# Spin_SCH.net
KiCad netlist of a schematic drawn in Altium Designer
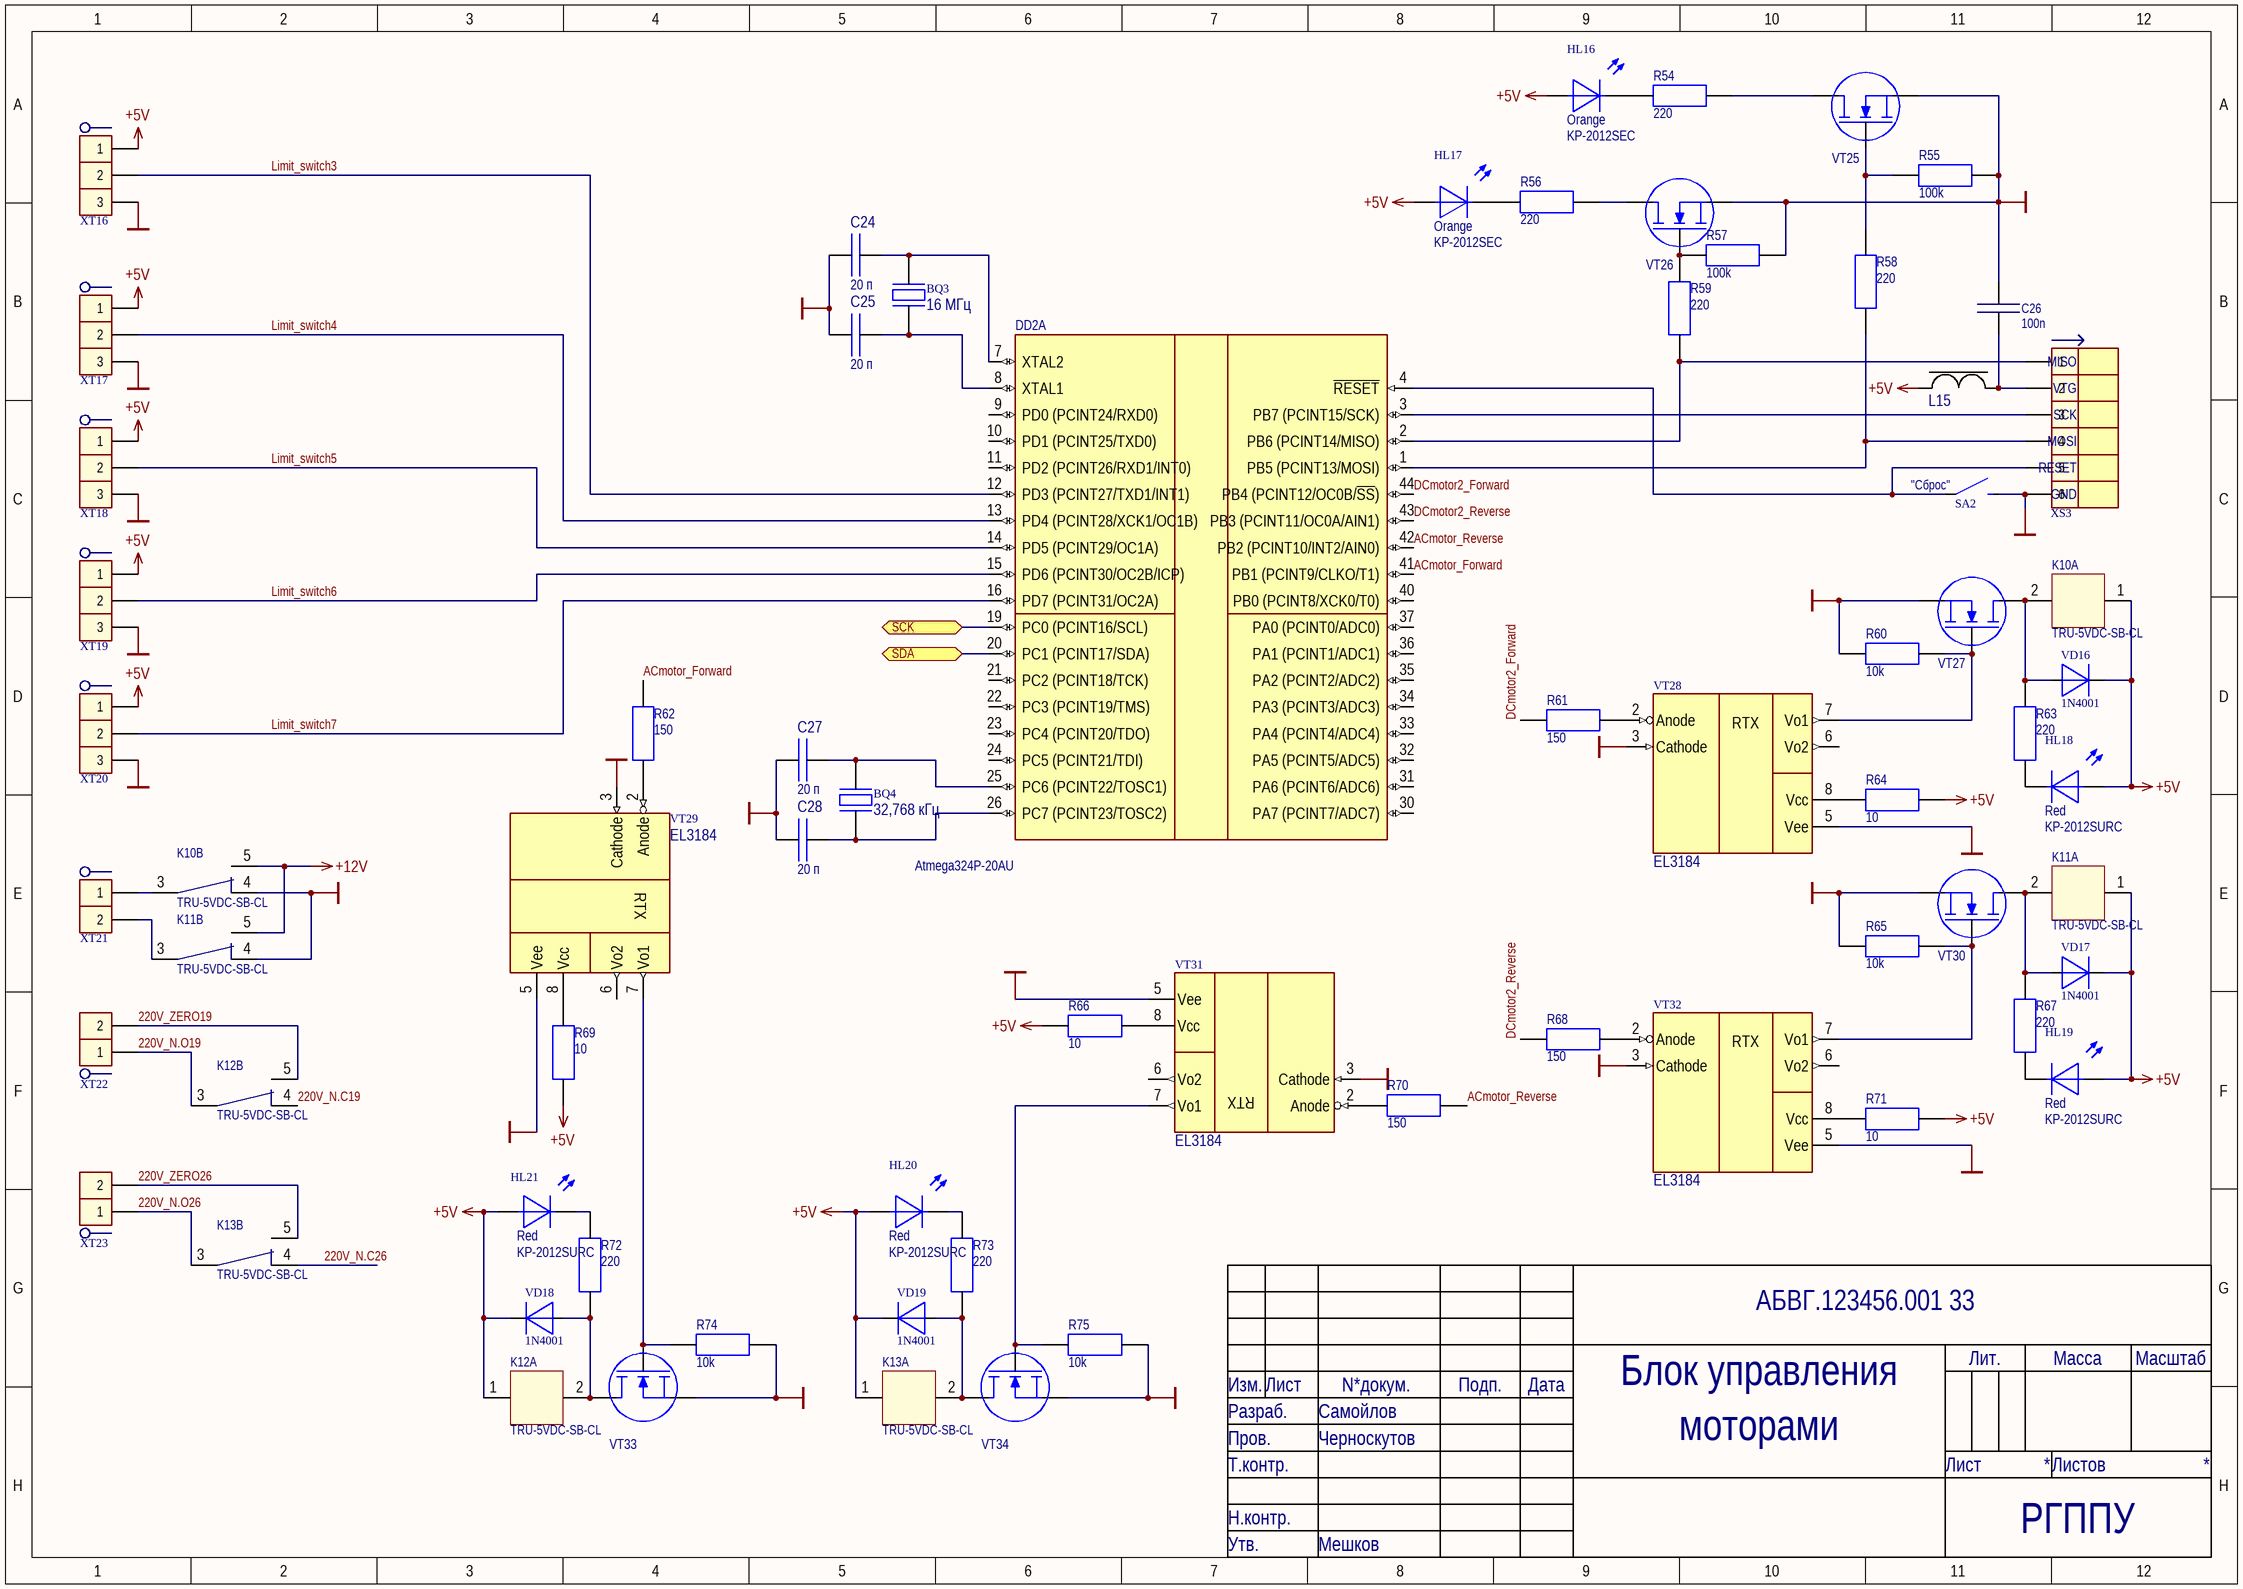
[diagram p0: Spin_SCH.SchDoc]

(export (version "E")
  (design (tool "Eeschema 10.0.6"))
  (components
    (comp (ref "BQ3")
      (value "16 МГц")
      (footprint "Piezoelectric:HC-49/S")
      (description "Piezoelectric elements")
      (fields
        (field (name "MANUFACTURER") "Taizhou")
        (field (name "MANUFACTURERPARTNUMBER") "16000 кГц 20ppm 20pF")
      )
      (libsource (lib "Piezoelectric") (part "Piezoelectric_16000"))
    )
    (comp (ref "BQ4")
      (value "32,768 кГц")
      (footprint "Piezoelectric:HC-49/S")
      (description "Piezoelectric elements")
      (fields
        (field (name "MANUFACTURER") "Taizhou")
        (field (name "MANUFACTURERPARTNUMBER") "16000 кГц 20ppm 20pF")
      )
      (libsource (lib "Piezoelectric") (part "Piezoelectric_16000"))
    )
    (comp (ref "C24")
      (value "20 п")
      (footprint "Cap:CAPC3216X05M")
      (description "20pF Bipolar cap")
      (fields
        (field (name "MANUFACTURERPARTNUMBER") "CC0603JRNP09BN200")
        (field (name "MANUFACTURER") "Yageo")
      )
      (libsource (lib "Cap") (part "p00020_050"))
    )
    (comp (ref "C25")
      (value "20 п")
      (footprint "Cap:CAPC3216X05M")
      (description "20pF Bipolar cap")
      (fields
        (field (name "MANUFACTURERPARTNUMBER") "CC0603JRNP09BN200")
        (field (name "MANUFACTURER") "Yageo")
      )
      (libsource (lib "Cap") (part "p00020_050"))
    )
    (comp (ref "C26")
      (value "100n")
      (footprint "SMDRC0805")
      (description "Generic capasitor non-polar")
      (fields (field (name "PARTNUMBER") "Capacitor 0805 100n"))
      (libsource (lib "library") (part "Capacitor"))
    )
    (comp (ref "C27")
      (value "20 п")
      (footprint "Cap:CAPC3216X05M")
      (description "20pF Bipolar cap")
      (fields
        (field (name "MANUFACTURERPARTNUMBER") "CC0603JRNP09BN200")
        (field (name "MANUFACTURER") "Yageo")
      )
      (libsource (lib "Cap") (part "p00020_050"))
    )
    (comp (ref "C28")
      (value "20 п")
      (footprint "Cap:CAPC3216X05M")
      (description "20pF Bipolar cap")
      (fields
        (field (name "MANUFACTURERPARTNUMBER") "CC0603JRNP09BN200")
        (field (name "MANUFACTURER") "Yageo")
      )
      (libsource (lib "Cap") (part "p00020_050"))
    )
    (comp (ref "DD2")
      (value "Atmega324P-20AU")
      (footprint "Atmel Microcontroller 8-Bit Automotive AVR:44ML_M")
      (description "Microcontroller 8-bit")
      (fields (field (name "MANUFACTURER") "Atmel") (field (name "MANUFACTURERPARTNUMBER") "Atmega324P-20AU"))
      (libsource (lib "Microcontrollers") (part "Atmega324P-20AU"))
    )
    (comp (ref "HL16")
      (value "Orange")
      (footprint "Indicator:DIOMELF2012M")
      (description "Diod LED SMD Orange")
      (fields (field (name "MANUFACTURERPARTNUMBER") "KP-2012SEC"))
      (libsource (lib "Indicator") (part "LED1_O"))
    )
    (comp (ref "HL17")
      (value "Orange")
      (footprint "Indicator:DIOMELF2012M")
      (description "Diod LED SMD Orange")
      (fields (field (name "MANUFACTURERPARTNUMBER") "KP-2012SEC"))
      (libsource (lib "Indicator") (part "LED1_O"))
    )
    (comp (ref "HL18")
      (value "Red")
      (footprint "Indicator:DIOMELF2012M")
      (description "Diod LED SMD Red")
      (fields (field (name "MANUFACTURERPARTNUMBER") "KP-2012SURC"))
      (libsource (lib "") (part "LED1_R_1"))
    )
    (comp (ref "HL19")
      (value "Red")
      (footprint "Indicator:DIOMELF2012M")
      (description "Diod LED SMD Red")
      (fields (field (name "MANUFACTURERPARTNUMBER") "KP-2012SURC"))
      (libsource (lib "") (part "LED1_R_1"))
    )
    (comp (ref "HL20")
      (value "Red")
      (footprint "Indicator:DIOMELF2012M")
      (description "Diod LED SMD Red")
      (fields (field (name "MANUFACTURERPARTNUMBER") "KP-2012SURC"))
      (libsource (lib "Indicator") (part "LED1_R"))
    )
    (comp (ref "HL21")
      (value "Red")
      (footprint "Indicator:DIOMELF2012M")
      (description "Diod LED SMD Red")
      (fields (field (name "MANUFACTURERPARTNUMBER") "KP-2012SURC"))
      (libsource (lib "Indicator") (part "LED1_R"))
    )
    (comp (ref "K10")
      (value "TRU-5VDC-SB-CL")
      (footprint "Switch:TRU-5VDC-SB-CL")
      (libsource (lib "") (part "TRU-5VDC-SB-CL_2"))
    )
    (comp (ref "K11")
      (value "TRU-5VDC-SB-CL")
      (footprint "Switch:TRU-5VDC-SB-CL")
      (libsource (lib "") (part "TRU-5VDC-SB-CL_2"))
    )
    (comp (ref "K12")
      (value "TRU-5VDC-SB-CL")
      (footprint "Switch:TRU-5VDC-SB-CL")
      (libsource (lib "") (part "TRU-5VDC-SB-CL_2"))
    )
    (comp (ref "K13")
      (value "TRU-5VDC-SB-CL")
      (footprint "Switch:TRU-5VDC-SB-CL")
      (libsource (lib "") (part "TRU-5VDC-SB-CL_2"))
    )
    (comp (ref "L15")
      (value "MPZ1608S181A")
      (footprint "Inductor:INDC0603X03M")
      (description "Ferrite Bead")
      (libsource (lib "Inductor") (part "Ferrite Bead"))
    )
    (comp (ref "R54")
      (value "220")
      (footprint "SMDRC0805")
      (description "Generic resistor")
      (fields (field (name "PARTNUMBER") "Resistor 0805 220"))
      (libsource (lib "library") (part "Resistor"))
    )
    (comp (ref "R55")
      (value "100k")
      (footprint "SMDRC0805")
      (description "Generic resistor")
      (fields (field (name "PARTNUMBER") "Resistor 0805 100k"))
      (libsource (lib "") (part "Resistor_3"))
    )
    (comp (ref "R56")
      (value "220")
      (footprint "SMDRC0805")
      (description "Generic resistor")
      (fields (field (name "PARTNUMBER") "Resistor 0805 220"))
      (libsource (lib "library") (part "Resistor"))
    )
    (comp (ref "R57")
      (value "100k")
      (footprint "SMDRC0805")
      (description "Generic resistor")
      (fields (field (name "PARTNUMBER") "Resistor 0805 100k"))
      (libsource (lib "") (part "Resistor_3"))
    )
    (comp (ref "R58")
      (value "220")
      (footprint "SMDRC0805")
      (description "Generic resistor")
      (fields (field (name "PARTNUMBER") "Resistor 0805 220"))
      (libsource (lib "") (part "Resistor_2"))
    )
    (comp (ref "R59")
      (value "220")
      (footprint "SMDRC0805")
      (description "Generic resistor")
      (fields (field (name "PARTNUMBER") "Resistor 0805 220"))
      (libsource (lib "") (part "Resistor_2"))
    )
    (comp (ref "R60")
      (value "10k")
      (footprint "SMDRC0805")
      (description "Generic resistor")
      (fields (field (name "PARTNUMBER") "Resistor 0805 10k"))
      (libsource (lib "") (part "Resistor_1"))
    )
    (comp (ref "R61")
      (value "150")
      (footprint "SMDRC0805")
      (description "Generic resistor")
      (fields (field (name "PARTNUMBER") "Resistor 0805 150"))
      (libsource (lib "") (part "Resistor_3"))
    )
    (comp (ref "R62")
      (value "150")
      (footprint "SMDRC0805")
      (description "Generic resistor")
      (fields (field (name "PARTNUMBER") "Resistor 0805 150"))
      (libsource (lib "") (part "Resistor_1"))
    )
    (comp (ref "R63")
      (value "220")
      (footprint "SMDRC0805")
      (description "Generic resistor")
      (fields (field (name "PARTNUMBER") "Resistor 0805 220"))
      (libsource (lib "library") (part "Resistor"))
    )
    (comp (ref "R64")
      (value "10")
      (footprint "SMDRC0805")
      (description "Generic resistor")
      (fields (field (name "PARTNUMBER") "Resistor 0805 10"))
      (libsource (lib "") (part "Resistor_3"))
    )
    (comp (ref "R65")
      (value "10k")
      (footprint "SMDRC0805")
      (description "Generic resistor")
      (fields (field (name "PARTNUMBER") "Resistor 0805 10k"))
      (libsource (lib "") (part "Resistor_1"))
    )
    (comp (ref "R66")
      (value "10")
      (footprint "SMDRC0805")
      (description "Generic resistor")
      (fields (field (name "PARTNUMBER") "Resistor 0805 10"))
      (libsource (lib "library") (part "Resistor"))
    )
    (comp (ref "R67")
      (value "220")
      (footprint "SMDRC0805")
      (description "Generic resistor")
      (fields (field (name "PARTNUMBER") "Resistor 0805 220"))
      (libsource (lib "library") (part "Resistor"))
    )
    (comp (ref "R68")
      (value "150")
      (footprint "SMDRC0805")
      (description "Generic resistor")
      (fields (field (name "PARTNUMBER") "Resistor 0805 150"))
      (libsource (lib "") (part "Resistor_3"))
    )
    (comp (ref "R69")
      (value "10")
      (footprint "SMDRC0805")
      (description "Generic resistor")
      (fields (field (name "PARTNUMBER") "Resistor 0805 10"))
      (libsource (lib "") (part "Resistor_1"))
    )
    (comp (ref "R70")
      (value "150")
      (footprint "SMDRC0805")
      (description "Generic resistor")
      (fields (field (name "PARTNUMBER") "Resistor 0805 150"))
      (libsource (lib "library") (part "Resistor"))
    )
    (comp (ref "R71")
      (value "10")
      (footprint "SMDRC0805")
      (description "Generic resistor")
      (fields (field (name "PARTNUMBER") "Resistor 0805 10"))
      (libsource (lib "") (part "Resistor_3"))
    )
    (comp (ref "R72")
      (value "220")
      (footprint "SMDRC0805")
      (description "Generic resistor")
      (fields (field (name "PARTNUMBER") "Resistor 0805 220"))
      (libsource (lib "") (part "Resistor_3"))
    )
    (comp (ref "R73")
      (value "220")
      (footprint "SMDRC0805")
      (description "Generic resistor")
      (fields (field (name "PARTNUMBER") "Resistor 0805 220"))
      (libsource (lib "") (part "Resistor_3"))
    )
    (comp (ref "R74")
      (value "10k")
      (footprint "SMDRC0805")
      (description "Generic resistor")
      (fields (field (name "PARTNUMBER") "Resistor 0805 10k"))
      (libsource (lib "") (part "Resistor_2"))
    )
    (comp (ref "R75")
      (value "10k")
      (footprint "SMDRC0805")
      (description "Generic resistor")
      (fields (field (name "PARTNUMBER") "Resistor 0805 10k"))
      (libsource (lib "") (part "Resistor_2"))
    )
    (comp (ref "SA2")
      (value "DTSM20-4.3")
      (footprint "Switch:DTSM20")
      (description "Switch open")
      (fields (field (name "MANUFACTURER") "Diptronics"))
      (libsource (lib "Switch") (part "Switch1_DTSM20-4.3"))
    )
    (comp (ref "VD16")
      (value "1N4001")
      (footprint "DIod:PinDiode")
      (description "Rectifying diode")
      (fields (field (name "MANUFACTURERPARTNUMBER") "1N4001"))
      (libsource (lib "Diod") (part "1N4001"))
    )
    (comp (ref "VD17")
      (value "1N4001")
      (footprint "DIod:PinDiode")
      (description "Rectifying diode")
      (fields (field (name "MANUFACTURERPARTNUMBER") "1N4001"))
      (libsource (lib "Diod") (part "1N4001"))
    )
    (comp (ref "VD18")
      (value "1N4001")
      (footprint "DIod:PinDiode")
      (description "Rectifying diode")
      (fields (field (name "MANUFACTURERPARTNUMBER") "1N4001"))
      (libsource (lib "Diod") (part "1N4001"))
    )
    (comp (ref "VD19")
      (value "1N4001")
      (footprint "DIod:PinDiode")
      (description "Rectifying diode")
      (fields (field (name "MANUFACTURERPARTNUMBER") "1N4001"))
      (libsource (lib "Diod") (part "1N4001"))
    )
    (comp (ref "VT25")
      (value "2N7002")
      (footprint "Standard:SOT23 (TO-236AB)")
      (description "60V, 300mA N-channel Trench MOSFET")
      (libsource (lib "Transistor") (part "2N7002 n-MOSFET"))
    )
    (comp (ref "VT26")
      (value "2N7002")
      (footprint "Standard:SOT23 (TO-236AB)")
      (description "60V, 300mA N-channel Trench MOSFET")
      (libsource (lib "Transistor") (part "2N7002 n-MOSFET"))
    )
    (comp (ref "VT27")
      (value "2N7002")
      (footprint "Standard:SOT23 (TO-236AB)")
      (description "60V, 300mA N-channel Trench MOSFET")
      (libsource (lib "Transistor") (part "2N7002 n-MOSFET"))
    )
    (comp (ref "VT28")
      (value "EL3184")
      (footprint "DIP8")
      (description "Optocouple IGBT driver")
      (fields
        (field (name "MANUFACTURER") "Everlight Electronics Co. Ltd")
        (field (name "MANUFACTURERPARTNUMBER") "EL3184")
      )
      (libsource (lib "") (part "EL3184_1"))
    )
    (comp (ref "VT29")
      (value "EL3184")
      (footprint "DIP8")
      (description "Optocouple IGBT driver")
      (fields
        (field (name "MANUFACTURER") "Everlight Electronics Co. Ltd")
        (field (name "MANUFACTURERPARTNUMBER") "EL3184")
      )
      (libsource (lib "Interface") (part "EL3184"))
    )
    (comp (ref "VT30")
      (value "2N7002")
      (footprint "Standard:SOT23 (TO-236AB)")
      (description "60V, 300mA N-channel Trench MOSFET")
      (libsource (lib "Transistor") (part "2N7002 n-MOSFET"))
    )
    (comp (ref "VT31")
      (value "EL3184")
      (footprint "DIP8")
      (description "Optocouple IGBT driver")
      (fields
        (field (name "MANUFACTURER") "Everlight Electronics Co. Ltd")
        (field (name "MANUFACTURERPARTNUMBER") "EL3184")
      )
      (libsource (lib "") (part "EL3184_2"))
    )
    (comp (ref "VT32")
      (value "EL3184")
      (footprint "DIP8")
      (description "Optocouple IGBT driver")
      (fields
        (field (name "MANUFACTURER") "Everlight Electronics Co. Ltd")
        (field (name "MANUFACTURERPARTNUMBER") "EL3184")
      )
      (libsource (lib "") (part "EL3184_1"))
    )
    (comp (ref "VT33")
      (value "2N7002")
      (footprint "Standard:SOT23 (TO-236AB)")
      (description "60V, 300mA N-channel Trench MOSFET")
      (libsource (lib "Transistor") (part "2N7002 n-MOSFET"))
    )
    (comp (ref "VT34")
      (value "2N7002")
      (footprint "Standard:SOT23 (TO-236AB)")
      (description "60V, 300mA N-channel Trench MOSFET")
      (libsource (lib "Transistor") (part "2N7002 n-MOSFET"))
    )
    (comp (ref "XS3")
      (value "IDC-06M")
      (footprint "Connector:IDC-06M")
      (description "SPI connector")
      (libsource (lib "Connector") (part "Con6_M IDC-06M_SPI"))
    )
    (comp (ref "XT16")
      (value "330-031-12")
      (footprint "Connector:330-031-12")
      (description "Demountable connection 3-pin")
      (fields (field (name "MANUFACTURER") "Degson Electronics Co., Ltd"))
      (libsource (lib "Connector") (part "Con3_D 330-031-12"))
    )
    (comp (ref "XT17")
      (value "330-031-12")
      (footprint "Connector:330-031-12")
      (description "Demountable connection 3-pin")
      (fields (field (name "MANUFACTURER") "Degson Electronics Co., Ltd"))
      (libsource (lib "Connector") (part "Con3_D 330-031-12"))
    )
    (comp (ref "XT18")
      (value "330-031-12")
      (footprint "Connector:330-031-12")
      (description "Demountable connection 3-pin")
      (fields (field (name "MANUFACTURER") "Degson Electronics Co., Ltd"))
      (libsource (lib "Connector") (part "Con3_D 330-031-12"))
    )
    (comp (ref "XT19")
      (value "330-031-12")
      (footprint "Connector:330-031-12")
      (description "Demountable connection 3-pin")
      (fields (field (name "MANUFACTURER") "Degson Electronics Co., Ltd"))
      (libsource (lib "Connector") (part "Con3_D 330-031-12"))
    )
    (comp (ref "XT20")
      (value "330-031-12")
      (footprint "Connector:330-031-12")
      (description "Demountable connection 3-pin")
      (fields (field (name "MANUFACTURER") "Degson Electronics Co., Ltd"))
      (libsource (lib "Connector") (part "Con3_D 330-031-12"))
    )
    (comp (ref "XT21")
      (value "330-021-12")
      (footprint "Connector:330-021-12")
      (description "Demountable connection  2-pin")
      (fields (field (name "MANUFACTURER") "Degson Electronics Co., Ltd"))
      (libsource (lib "Connector") (part "Con2_D 330-021-12"))
    )
    (comp (ref "XT22")
      (value "305-021-12")
      (footprint "330-021-12")
      (description "Demountable connection  2-pin")
      (fields (field (name "MANUFACTURER") "Degson Electronics Co., Ltd"))
      (libsource (lib "") (part "Con2_D 330-021-12_1"))
    )
    (comp (ref "XT23")
      (value "305-021-12")
      (footprint "330-021-12")
      (description "Demountable connection  2-pin")
      (fields (field (name "MANUFACTURER") "Degson Electronics Co., Ltd"))
      (libsource (lib "") (part "Con2_D 330-021-12_1"))
    )
  )
  (nets
    (net (code "1") (name "+5V") (class "Default")
      (node (ref "HL16") (pin "1") (pinfunction "1_1") (pintype "passive"))
      (node (ref "HL17") (pin "1") (pinfunction "1_1") (pintype "passive"))
      (node (ref "HL18") (pin "1") (pinfunction "1_1") (pintype "passive"))
      (node (ref "HL19") (pin "1") (pinfunction "1_1") (pintype "passive"))
      (node (ref "HL20") (pin "1") (pinfunction "1_1") (pintype "passive"))
      (node (ref "HL21") (pin "1") (pinfunction "1_1") (pintype "passive"))
      (node (ref "K10") (pin "1") (pinfunction "1_1") (pintype "passive"))
      (node (ref "K11") (pin "1") (pinfunction "1_1") (pintype "passive"))
      (node (ref "K12") (pin "1") (pinfunction "1_1") (pintype "passive"))
      (node (ref "K13") (pin "1") (pinfunction "1_1") (pintype "passive"))
      (node (ref "L15") (pin "1") (pinfunction "1_1") (pintype "passive"))
      (node (ref "R64") (pin "2") (pinfunction "2_2") (pintype "passive"))
      (node (ref "R66") (pin "2") (pinfunction "2_2") (pintype "passive"))
      (node (ref "R69") (pin "2") (pinfunction "2_2") (pintype "passive"))
      (node (ref "R71") (pin "2") (pinfunction "2_2") (pintype "passive"))
      (node (ref "VD16") (pin "K") (pinfunction "K_K") (pintype "passive"))
      (node (ref "VD17") (pin "K") (pinfunction "K_K") (pintype "passive"))
      (node (ref "VD18") (pin "K") (pinfunction "K_K") (pintype "passive"))
      (node (ref "VD19") (pin "K") (pinfunction "K_K") (pintype "passive"))
      (node (ref "XT16") (pin "1") (pinfunction "1_1") (pintype "passive"))
      (node (ref "XT17") (pin "1") (pinfunction "1_1") (pintype "passive"))
      (node (ref "XT18") (pin "1") (pinfunction "1_1") (pintype "passive"))
      (node (ref "XT19") (pin "1") (pinfunction "1_1") (pintype "passive"))
      (node (ref "XT20") (pin "1") (pinfunction "1_1") (pintype "passive"))
    )
    (net (code "2") (name "+12V") (class "Default")
      (node (ref "K10") (pin "5") (pinfunction "5_5") (pintype "passive"))
      (node (ref "K11") (pin "5") (pinfunction "5_5") (pintype "passive"))
    )
    (net (code "3") (name "/220V_N.C19") (class "Default")
      (node (ref "K12") (pin "4") (pinfunction "4_4") (pintype "passive"))
    )
    (net (code "4") (name "/220V_N.C26") (class "Default")
      (node (ref "K13") (pin "4") (pinfunction "4_4") (pintype "passive"))
    )
    (net (code "5") (name "/220V_N.O19") (class "Default")
      (node (ref "K12") (pin "3") (pinfunction "3_3") (pintype "passive"))
      (node (ref "XT22") (pin "1") (pinfunction "1_1") (pintype "passive"))
    )
    (net (code "6") (name "/220V_N.O26") (class "Default")
      (node (ref "K13") (pin "3") (pinfunction "3_3") (pintype "passive"))
      (node (ref "XT23") (pin "1") (pinfunction "1_1") (pintype "passive"))
    )
    (net (code "7") (name "/220V_ZERO19") (class "Default")
      (node (ref "K12") (pin "5") (pinfunction "5_5") (pintype "passive"))
      (node (ref "XT22") (pin "2") (pinfunction "2_2") (pintype "passive"))
    )
    (net (code "8") (name "/220V_ZERO26") (class "Default")
      (node (ref "K13") (pin "5") (pinfunction "5_5") (pintype "passive"))
      (node (ref "XT23") (pin "2") (pinfunction "2_2") (pintype "passive"))
    )
    (net (code "9") (name "/ACmotor_Forward") (class "Default")
      (node (ref "DD2") (pin "41") (pinfunction "PB1_(PCINT9/CLKO/T1)_41") (pintype "bidirectional"))
      (node (ref "R62") (pin "1") (pinfunction "1_1") (pintype "passive"))
    )
    (net (code "10") (name "/ACmotor_Reverse") (class "Default")
      (node (ref "DD2") (pin "42") (pinfunction "PB2_(PCINT10/INT2/AIN0)_42") (pintype "bidirectional"))
      (node (ref "R70") (pin "1") (pinfunction "1_1") (pintype "passive"))
    )
    (net (code "11") (name "/DCmotor2_Forward") (class "Default")
      (node (ref "DD2") (pin "44") (pinfunction "PB4_(PCINT12/OC0B/~{SS})_44") (pintype "bidirectional"))
      (node (ref "R61") (pin "1") (pinfunction "1_1") (pintype "passive"))
    )
    (net (code "12") (name "/DCmotor2_Reverse") (class "Default")
      (node (ref "DD2") (pin "43") (pinfunction "PB3_(PCINT11/OC0A/AIN1)_43") (pintype "bidirectional"))
      (node (ref "R68") (pin "1") (pinfunction "1_1") (pintype "passive"))
    )
    (net (code "13") (name "/Limit_switch3") (class "Default")
      (node (ref "DD2") (pin "12") (pinfunction "PD3_(PCINT27/TXD1/INT1)_12") (pintype "bidirectional"))
      (node (ref "XT16") (pin "2") (pinfunction "2_2") (pintype "passive"))
    )
    (net (code "14") (name "/Limit_switch4") (class "Default")
      (node (ref "DD2") (pin "13") (pinfunction "PD4_(PCINT28/XCK1/OC1B)_13") (pintype "bidirectional"))
      (node (ref "XT17") (pin "2") (pinfunction "2_2") (pintype "passive"))
    )
    (net (code "15") (name "/Limit_switch5") (class "Default")
      (node (ref "DD2") (pin "14") (pinfunction "PD5_(PCINT29/OC1A)_14") (pintype "bidirectional"))
      (node (ref "XT18") (pin "2") (pinfunction "2_2") (pintype "passive"))
    )
    (net (code "16") (name "/Limit_switch6") (class "Default")
      (node (ref "DD2") (pin "15") (pinfunction "PD6_(PCINT30/OC2B/ICP)_15") (pintype "bidirectional"))
      (node (ref "XT19") (pin "2") (pinfunction "2_2") (pintype "passive"))
    )
    (net (code "17") (name "/Limit_switch7") (class "Default")
      (node (ref "DD2") (pin "16") (pinfunction "PD7_(PCINT31/OC2A)_16") (pintype "bidirectional"))
      (node (ref "XT20") (pin "2") (pinfunction "2_2") (pintype "passive"))
    )
    (net (code "18") (name "/SCK") (class "Default")
      (node (ref "DD2") (pin "19") (pinfunction "PC0_(PCINT16/SCL)_19") (pintype "bidirectional"))
    )
    (net (code "19") (name "/SDA") (class "Default")
      (node (ref "DD2") (pin "20") (pinfunction "PC1_(PCINT17/SDA)_20") (pintype "bidirectional"))
    )
    (net (code "20") (name "GND") (class "Default")
      (node (ref "C24") (pin "2") (pinfunction "2_2") (pintype "passive"))
      (node (ref "C25") (pin "2") (pinfunction "2_2") (pintype "passive"))
      (node (ref "C26") (pin "2") (pintype "passive"))
      (node (ref "C27") (pin "2") (pinfunction "2_2") (pintype "passive"))
      (node (ref "C28") (pin "2") (pinfunction "2_2") (pintype "passive"))
      (node (ref "K10") (pin "4") (pinfunction "4_4") (pintype "passive"))
      (node (ref "K11") (pin "4") (pinfunction "4_4") (pintype "passive"))
      (node (ref "R55") (pin "2") (pinfunction "2_2") (pintype "passive"))
      (node (ref "R57") (pin "2") (pinfunction "2_2") (pintype "passive"))
      (node (ref "R60") (pin "2") (pinfunction "2_2") (pintype "passive"))
      (node (ref "R65") (pin "2") (pinfunction "2_2") (pintype "passive"))
      (node (ref "R74") (pin "2") (pinfunction "2_2") (pintype "passive"))
      (node (ref "R75") (pin "2") (pinfunction "2_2") (pintype "passive"))
      (node (ref "SA2") (pin "2") (pinfunction "2_2") (pintype "passive"))
      (node (ref "VT25") (pin "2") (pinfunction "S_2") (pintype "passive"))
      (node (ref "VT26") (pin "2") (pinfunction "S_2") (pintype "passive"))
      (node (ref "VT27") (pin "2") (pinfunction "S_2") (pintype "passive"))
      (node (ref "VT28") (pin "3") (pinfunction "Cathode_3") (pintype "input"))
      (node (ref "VT28") (pin "5") (pinfunction "Vee_5") (pintype "power_in"))
      (node (ref "VT29") (pin "3") (pinfunction "Cathode_3") (pintype "input"))
      (node (ref "VT29") (pin "5") (pinfunction "Vee_5") (pintype "power_in"))
      (node (ref "VT30") (pin "2") (pinfunction "S_2") (pintype "passive"))
      (node (ref "VT31") (pin "3") (pinfunction "Cathode_3") (pintype "input"))
      (node (ref "VT31") (pin "5") (pinfunction "Vee_5") (pintype "power_in"))
      (node (ref "VT32") (pin "3") (pinfunction "Cathode_3") (pintype "input"))
      (node (ref "VT32") (pin "5") (pinfunction "Vee_5") (pintype "power_in"))
      (node (ref "VT33") (pin "2") (pinfunction "S_2") (pintype "passive"))
      (node (ref "VT34") (pin "2") (pinfunction "S_2") (pintype "passive"))
      (node (ref "XS3") (pin "6") (pinfunction "6_6") (pintype "passive"))
      (node (ref "XT16") (pin "3") (pinfunction "3_3") (pintype "passive"))
      (node (ref "XT17") (pin "3") (pinfunction "3_3") (pintype "passive"))
      (node (ref "XT18") (pin "3") (pinfunction "3_3") (pintype "passive"))
      (node (ref "XT19") (pin "3") (pinfunction "3_3") (pintype "passive"))
      (node (ref "XT20") (pin "3") (pinfunction "3_3") (pintype "passive"))
    )
    (net (code "21") (name "Net-(C26-Pad1)") (class "Default")
      (node (ref "C26") (pin "1") (pintype "passive"))
      (node (ref "L15") (pin "2") (pinfunction "2_2") (pintype "passive"))
      (node (ref "XS3") (pin "2") (pinfunction "2_2") (pintype "passive"))
    )
    (net (code "22") (name "Net-(DD2A-PB5_(PCINT13{slash}MOSI))") (class "Default")
      (node (ref "DD2") (pin "1") (pinfunction "PB5_(PCINT13/MOSI)_1") (pintype "bidirectional"))
      (node (ref "R58") (pin "1") (pinfunction "1_1") (pintype "passive"))
      (node (ref "XS3") (pin "4") (pinfunction "4_4") (pintype "passive"))
    )
    (net (code "23") (name "Net-(DD2A-PB6_(PCINT14{slash}MISO))") (class "Default")
      (node (ref "DD2") (pin "2") (pinfunction "PB6_(PCINT14/MISO)_2") (pintype "bidirectional"))
      (node (ref "R59") (pin "1") (pinfunction "1_1") (pintype "passive"))
      (node (ref "XS3") (pin "1") (pinfunction "1_1") (pintype "passive"))
    )
    (net (code "24") (name "Net-(DD2A-PB7_(PCINT15{slash}SCK))") (class "Default")
      (node (ref "DD2") (pin "3") (pinfunction "PB7_(PCINT15/SCK)_3") (pintype "bidirectional"))
      (node (ref "XS3") (pin "3") (pinfunction "3_3") (pintype "passive"))
    )
    (net (code "25") (name "Net-(DD2A-PC6_(PCINT22{slash}TOSC1))") (class "Default")
      (node (ref "BQ4") (pin "2") (pinfunction "2_2") (pintype "passive"))
      (node (ref "C27") (pin "1") (pinfunction "1_1") (pintype "passive"))
      (node (ref "DD2") (pin "25") (pinfunction "PC6_(PCINT22/TOSC1)_25") (pintype "bidirectional"))
    )
    (net (code "26") (name "Net-(DD2A-PC7_(PCINT23{slash}TOSC2))") (class "Default")
      (node (ref "BQ4") (pin "1") (pinfunction "1_1") (pintype "passive"))
      (node (ref "C28") (pin "1") (pinfunction "1_1") (pintype "passive"))
      (node (ref "DD2") (pin "26") (pinfunction "PC7_(PCINT23/TOSC2)_26") (pintype "bidirectional"))
    )
    (net (code "27") (name "Net-(DD2A-XTAL1)") (class "Default")
      (node (ref "BQ3") (pin "1") (pinfunction "1_1") (pintype "passive"))
      (node (ref "C25") (pin "1") (pinfunction "1_1") (pintype "passive"))
      (node (ref "DD2") (pin "8") (pinfunction "XTAL1_8") (pintype "bidirectional"))
    )
    (net (code "28") (name "Net-(DD2A-XTAL2)") (class "Default")
      (node (ref "BQ3") (pin "2") (pinfunction "2_2") (pintype "passive"))
      (node (ref "C24") (pin "1") (pinfunction "1_1") (pintype "passive"))
      (node (ref "DD2") (pin "7") (pinfunction "XTAL2_7") (pintype "bidirectional"))
    )
    (net (code "29") (name "Net-(DD2A-~{RESET})") (class "Default")
      (node (ref "DD2") (pin "4") (pinfunction "~{RESET}_4") (pintype "input"))
      (node (ref "SA2") (pin "1") (pinfunction "1_1") (pintype "passive"))
      (node (ref "XS3") (pin "5") (pinfunction "5_5") (pintype "passive"))
    )
    (net (code "30") (name "Net-(HL16-Pad2)") (class "Default")
      (node (ref "HL16") (pin "2") (pinfunction "2_2") (pintype "passive"))
      (node (ref "R54") (pin "2") (pinfunction "2_2") (pintype "passive"))
    )
    (net (code "31") (name "Net-(HL17-Pad2)") (class "Default")
      (node (ref "HL17") (pin "2") (pinfunction "2_2") (pintype "passive"))
      (node (ref "R56") (pin "2") (pinfunction "2_2") (pintype "passive"))
    )
    (net (code "32") (name "Net-(HL18-Pad2)") (class "Default")
      (node (ref "HL18") (pin "2") (pinfunction "2_2") (pintype "passive"))
      (node (ref "R63") (pin "2") (pinfunction "2_2") (pintype "passive"))
    )
    (net (code "33") (name "Net-(HL19-Pad2)") (class "Default")
      (node (ref "HL19") (pin "2") (pinfunction "2_2") (pintype "passive"))
      (node (ref "R67") (pin "2") (pinfunction "2_2") (pintype "passive"))
    )
    (net (code "34") (name "Net-(HL20-Pad2)") (class "Default")
      (node (ref "HL20") (pin "2") (pinfunction "2_2") (pintype "passive"))
      (node (ref "R73") (pin "2") (pinfunction "2_2") (pintype "passive"))
    )
    (net (code "35") (name "Net-(HL21-Pad2)") (class "Default")
      (node (ref "HL21") (pin "2") (pinfunction "2_2") (pintype "passive"))
      (node (ref "R72") (pin "2") (pinfunction "2_2") (pintype "passive"))
    )
    (net (code "36") (name "Net-(K10-Pad3)") (class "Default")
      (node (ref "K10") (pin "3") (pinfunction "3_3") (pintype "passive"))
      (node (ref "XT21") (pin "1") (pinfunction "1_1") (pintype "passive"))
    )
    (net (code "37") (name "Net-(K11-Pad3)") (class "Default")
      (node (ref "K11") (pin "3") (pinfunction "3_3") (pintype "passive"))
      (node (ref "XT21") (pin "2") (pinfunction "2_2") (pintype "passive"))
    )
    (net (code "38") (name "Net-(VT25-D)") (class "Default")
      (node (ref "R54") (pin "1") (pinfunction "1_1") (pintype "passive"))
      (node (ref "VT25") (pin "3") (pinfunction "D_3") (pintype "passive"))
    )
    (net (code "39") (name "Net-(VT25-G)") (class "Default")
      (node (ref "R55") (pin "1") (pinfunction "1_1") (pintype "passive"))
      (node (ref "R58") (pin "2") (pinfunction "2_2") (pintype "passive"))
      (node (ref "VT25") (pin "1") (pinfunction "G_1") (pintype "passive"))
    )
    (net (code "40") (name "Net-(VT26-D)") (class "Default")
      (node (ref "R56") (pin "1") (pinfunction "1_1") (pintype "passive"))
      (node (ref "VT26") (pin "3") (pinfunction "D_3") (pintype "passive"))
    )
    (net (code "41") (name "Net-(VT26-G)") (class "Default")
      (node (ref "R57") (pin "1") (pinfunction "1_1") (pintype "passive"))
      (node (ref "R59") (pin "2") (pinfunction "2_2") (pintype "passive"))
      (node (ref "VT26") (pin "1") (pinfunction "G_1") (pintype "passive"))
    )
    (net (code "42") (name "Net-(VT27-D)") (class "Default")
      (node (ref "K10") (pin "2") (pinfunction "2_2") (pintype "passive"))
      (node (ref "R63") (pin "1") (pinfunction "1_1") (pintype "passive"))
      (node (ref "VD16") (pin "A") (pinfunction "A_A") (pintype "passive"))
      (node (ref "VT27") (pin "3") (pinfunction "D_3") (pintype "passive"))
    )
    (net (code "43") (name "Net-(VT27-G)") (class "Default")
      (node (ref "R60") (pin "1") (pinfunction "1_1") (pintype "passive"))
      (node (ref "VT27") (pin "1") (pinfunction "G_1") (pintype "passive"))
      (node (ref "VT28") (pin "7") (pinfunction "Vo1_7") (pintype "output"))
    )
    (net (code "44") (name "Net-(VT28-Anode)") (class "Default")
      (node (ref "R61") (pin "2") (pinfunction "2_2") (pintype "passive"))
      (node (ref "VT28") (pin "2") (pinfunction "Anode_2") (pintype "input"))
    )
    (net (code "45") (name "Net-(VT28-Vcc)") (class "Default")
      (node (ref "R64") (pin "1") (pinfunction "1_1") (pintype "passive"))
      (node (ref "VT28") (pin "8") (pinfunction "Vcc_8") (pintype "power_in"))
    )
    (net (code "46") (name "Net-(VT29-Anode)") (class "Default")
      (node (ref "R62") (pin "2") (pinfunction "2_2") (pintype "passive"))
      (node (ref "VT29") (pin "2") (pinfunction "Anode_2") (pintype "input"))
    )
    (net (code "47") (name "Net-(VT29-Vcc)") (class "Default")
      (node (ref "R69") (pin "1") (pinfunction "1_1") (pintype "passive"))
      (node (ref "VT29") (pin "8") (pinfunction "Vcc_8") (pintype "power_in"))
    )
    (net (code "48") (name "Net-(VT29-Vo1)") (class "Default")
      (node (ref "R74") (pin "1") (pinfunction "1_1") (pintype "passive"))
      (node (ref "VT29") (pin "7") (pinfunction "Vo1_7") (pintype "output"))
      (node (ref "VT33") (pin "1") (pinfunction "G_1") (pintype "passive"))
    )
    (net (code "49") (name "Net-(VT30-D)") (class "Default")
      (node (ref "K11") (pin "2") (pinfunction "2_2") (pintype "passive"))
      (node (ref "R67") (pin "1") (pinfunction "1_1") (pintype "passive"))
      (node (ref "VD17") (pin "A") (pinfunction "A_A") (pintype "passive"))
      (node (ref "VT30") (pin "3") (pinfunction "D_3") (pintype "passive"))
    )
    (net (code "50") (name "Net-(VT30-G)") (class "Default")
      (node (ref "R65") (pin "1") (pinfunction "1_1") (pintype "passive"))
      (node (ref "VT30") (pin "1") (pinfunction "G_1") (pintype "passive"))
      (node (ref "VT32") (pin "7") (pinfunction "Vo1_7") (pintype "output"))
    )
    (net (code "51") (name "Net-(VT31-Anode)") (class "Default")
      (node (ref "R70") (pin "2") (pinfunction "2_2") (pintype "passive"))
      (node (ref "VT31") (pin "2") (pinfunction "Anode_2") (pintype "input"))
    )
    (net (code "52") (name "Net-(VT31-Vcc)") (class "Default")
      (node (ref "R66") (pin "1") (pinfunction "1_1") (pintype "passive"))
      (node (ref "VT31") (pin "8") (pinfunction "Vcc_8") (pintype "power_in"))
    )
    (net (code "53") (name "Net-(VT31-Vo1)") (class "Default")
      (node (ref "R75") (pin "1") (pinfunction "1_1") (pintype "passive"))
      (node (ref "VT31") (pin "7") (pinfunction "Vo1_7") (pintype "output"))
      (node (ref "VT34") (pin "1") (pinfunction "G_1") (pintype "passive"))
    )
    (net (code "54") (name "Net-(VT32-Anode)") (class "Default")
      (node (ref "R68") (pin "2") (pinfunction "2_2") (pintype "passive"))
      (node (ref "VT32") (pin "2") (pinfunction "Anode_2") (pintype "input"))
    )
    (net (code "55") (name "Net-(VT32-Vcc)") (class "Default")
      (node (ref "R71") (pin "1") (pinfunction "1_1") (pintype "passive"))
      (node (ref "VT32") (pin "8") (pinfunction "Vcc_8") (pintype "power_in"))
    )
    (net (code "56") (name "Net-(VT33-D)") (class "Default")
      (node (ref "K12") (pin "2") (pinfunction "2_2") (pintype "passive"))
      (node (ref "R72") (pin "1") (pinfunction "1_1") (pintype "passive"))
      (node (ref "VD18") (pin "A") (pinfunction "A_A") (pintype "passive"))
      (node (ref "VT33") (pin "3") (pinfunction "D_3") (pintype "passive"))
    )
    (net (code "57") (name "Net-(VT34-D)") (class "Default")
      (node (ref "K13") (pin "2") (pinfunction "2_2") (pintype "passive"))
      (node (ref "R73") (pin "1") (pinfunction "1_1") (pintype "passive"))
      (node (ref "VD19") (pin "A") (pinfunction "A_A") (pintype "passive"))
      (node (ref "VT34") (pin "3") (pinfunction "D_3") (pintype "passive"))
    )
    (net (code "58") (name "unconnected-(DD2A-PA0_(PCINT0{slash}ADC0)-Pad37)") (class "Default")
      (node (ref "DD2") (pin "37") (pinfunction "PA0_(PCINT0/ADC0)_37") (pintype "bidirectional"))
    )
    (net (code "59") (name "unconnected-(DD2A-PA1_(PCINT1{slash}ADC1)-Pad36)") (class "Default")
      (node (ref "DD2") (pin "36") (pinfunction "PA1_(PCINT1/ADC1)_36") (pintype "bidirectional"))
    )
    (net (code "60") (name "unconnected-(DD2A-PA2_(PCINT2{slash}ADC2)-Pad35)") (class "Default")
      (node (ref "DD2") (pin "35") (pinfunction "PA2_(PCINT2/ADC2)_35") (pintype "bidirectional"))
    )
    (net (code "61") (name "unconnected-(DD2A-PA3_(PCINT3{slash}ADC3)-Pad34)") (class "Default")
      (node (ref "DD2") (pin "34") (pinfunction "PA3_(PCINT3/ADC3)_34") (pintype "bidirectional"))
    )
    (net (code "62") (name "unconnected-(DD2A-PA4_(PCINT4{slash}ADC4)-Pad33)") (class "Default")
      (node (ref "DD2") (pin "33") (pinfunction "PA4_(PCINT4/ADC4)_33") (pintype "bidirectional"))
    )
    (net (code "63") (name "unconnected-(DD2A-PA5_(PCINT5{slash}ADC5)-Pad32)") (class "Default")
      (node (ref "DD2") (pin "32") (pinfunction "PA5_(PCINT5/ADC5)_32") (pintype "bidirectional"))
    )
    (net (code "64") (name "unconnected-(DD2A-PA6_(PCINT6{slash}ADC6)-Pad31)") (class "Default")
      (node (ref "DD2") (pin "31") (pinfunction "PA6_(PCINT6/ADC6)_31") (pintype "bidirectional"))
    )
    (net (code "65") (name "unconnected-(DD2A-PA7_(PCINT7{slash}ADC7)-Pad30)") (class "Default")
      (node (ref "DD2") (pin "30") (pinfunction "PA7_(PCINT7/ADC7)_30") (pintype "bidirectional"))
    )
    (net (code "66") (name "unconnected-(DD2A-PB0_(PCINT8{slash}XCK0{slash}T0)-Pad40)") (class "Default")
      (node (ref "DD2") (pin "40") (pinfunction "PB0_(PCINT8/XCK0/T0)_40") (pintype "bidirectional"))
    )
    (net (code "67") (name "unconnected-(DD2A-PC2_(PCINT18{slash}TCK)-Pad21)") (class "Default")
      (node (ref "DD2") (pin "21") (pinfunction "PC2_(PCINT18/TCK)_21") (pintype "bidirectional"))
    )
    (net (code "68") (name "unconnected-(DD2A-PC3_(PCINT19{slash}TMS)-Pad22)") (class "Default")
      (node (ref "DD2") (pin "22") (pinfunction "PC3_(PCINT19/TMS)_22") (pintype "bidirectional"))
    )
    (net (code "69") (name "unconnected-(DD2A-PC4_(PCINT20{slash}TDO)-Pad23)") (class "Default")
      (node (ref "DD2") (pin "23") (pinfunction "PC4_(PCINT20/TDO)_23") (pintype "bidirectional"))
    )
    (net (code "70") (name "unconnected-(DD2A-PC5_(PCINT21{slash}TDI)-Pad24)") (class "Default")
      (node (ref "DD2") (pin "24") (pinfunction "PC5_(PCINT21/TDI)_24") (pintype "bidirectional"))
    )
    (net (code "71") (name "unconnected-(DD2A-PD0_(PCINT24{slash}RXD0)-Pad9)") (class "Default")
      (node (ref "DD2") (pin "9") (pinfunction "PD0_(PCINT24/RXD0)_9") (pintype "bidirectional"))
    )
    (net (code "72") (name "unconnected-(DD2A-PD1_(PCINT25{slash}TXD0)-Pad10)") (class "Default")
      (node (ref "DD2") (pin "10") (pinfunction "PD1_(PCINT25/TXD0)_10") (pintype "bidirectional"))
    )
    (net (code "73") (name "unconnected-(DD2A-PD2_(PCINT26{slash}RXD1{slash}INT0)-Pad11)") (class "Default")
      (node (ref "DD2") (pin "11") (pinfunction "PD2_(PCINT26/RXD1/INT0)_11") (pintype "bidirectional"))
    )
    (net (code "74") (name "unconnected-(VT28-Vo2-Pad6)") (class "Default")
      (node (ref "VT28") (pin "6") (pinfunction "Vo2_6") (pintype "output"))
    )
    (net (code "75") (name "unconnected-(VT29-Vo2-Pad6)") (class "Default")
      (node (ref "VT29") (pin "6") (pinfunction "Vo2_6") (pintype "output"))
    )
    (net (code "76") (name "unconnected-(VT31-Vo2-Pad6)") (class "Default")
      (node (ref "VT31") (pin "6") (pinfunction "Vo2_6") (pintype "output"))
    )
    (net (code "77") (name "unconnected-(VT32-Vo2-Pad6)") (class "Default")
      (node (ref "VT32") (pin "6") (pinfunction "Vo2_6") (pintype "output"))
    )
  )
)
